# rfid-access-control.net
KiCad netlist of a schematic drawn in EAGLE
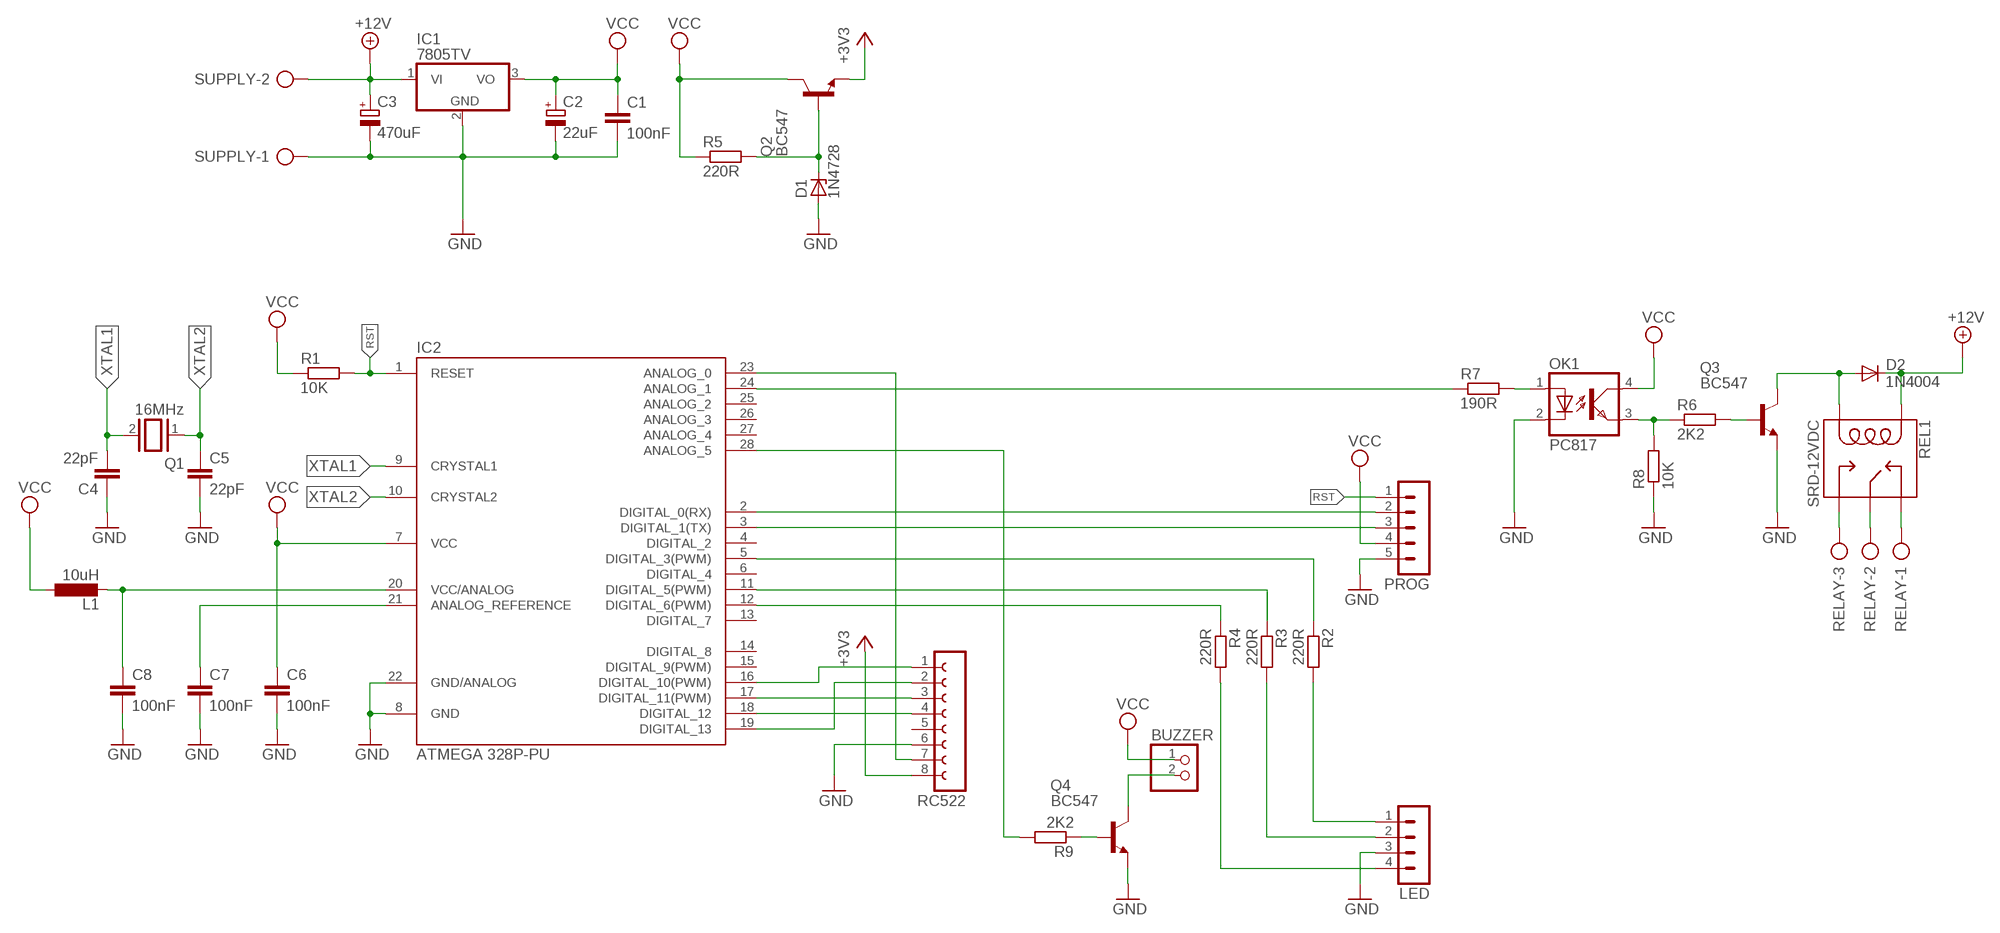
[diagram p0: schematic, sheet 1]

(export (version "E")
  (design (tool "Eeschema 10.0.6"))
  (components
    (comp (ref "BUZZER")
      (value "PINHD-1X2")
      (footprint "eagle-import:1X02")
      (libsource (lib "eagle-import") (part "PINHD-1X2"))
    )
    (comp (ref "C1")
      (value "100nF")
      (footprint "eagle-import:C025-025X050")
      (libsource (lib "eagle-import") (part "C-EU025-025X050"))
    )
    (comp (ref "C2")
      (value "22uF")
      (footprint "eagle-import:E2,5-7")
      (libsource (lib "eagle-import") (part "CPOL-EUE2.5-7"))
    )
    (comp (ref "C3")
      (value "470uF")
      (footprint "eagle-import:E2,5-7")
      (libsource (lib "eagle-import") (part "CPOL-EUE2.5-7"))
    )
    (comp (ref "C4")
      (value "22pF")
      (footprint "eagle-import:C025-025X050")
      (libsource (lib "eagle-import") (part "C-EU025-025X050"))
    )
    (comp (ref "C5")
      (value "22pF")
      (footprint "eagle-import:C025-025X050")
      (libsource (lib "eagle-import") (part "C-EU025-025X050"))
    )
    (comp (ref "C6")
      (value "100nF")
      (footprint "eagle-import:C025-025X050")
      (libsource (lib "eagle-import") (part "C-EU025-025X050"))
    )
    (comp (ref "C7")
      (value "100nF")
      (footprint "eagle-import:C025-025X050")
      (libsource (lib "eagle-import") (part "C-EU025-025X050"))
    )
    (comp (ref "C8")
      (value "100nF")
      (footprint "eagle-import:C025-025X050")
      (libsource (lib "eagle-import") (part "C-EU025-025X050"))
    )
    (comp (ref "D1")
      (value "1N4728")
      (footprint "eagle-import:DO41Z10")
      (libsource (lib "eagle-import") (part "1N4728"))
    )
    (comp (ref "D2")
      (value "1N4004")
      (footprint "eagle-import:DO41-10")
      (libsource (lib "eagle-import") (part "1N4004"))
    )
    (comp (ref "IC1")
      (value "7805TV")
      (footprint "eagle-import:TO220V")
      (libsource (lib "eagle-import") (part "78TV05"))
    )
    (comp (ref "IC2")
      (value "ATMEGA 328P-PU")
      (footprint "eagle-import:DIL28-3")
      (libsource (lib "eagle-import") (part "ATMEGA168-PU"))
    )
    (comp (ref "L1")
      (value "10uH")
      (footprint "eagle-import:0207_7")
      (libsource (lib "eagle-import") (part "L-EU0207/7"))
    )
    (comp (ref "LED")
      (value "MA04-1")
      (footprint "eagle-import:MA04-1")
      (libsource (lib "eagle-import") (part "MA04-1"))
    )
    (comp (ref "OK1")
      (value "PC817")
      (footprint "eagle-import:DIL04")
      (fields (field (name "MPN") "PC817X4J000F"))
      (libsource (lib "eagle-import") (part "PC817"))
    )
    (comp (ref "PROG")
      (value "MA05-1")
      (footprint "eagle-import:MA05-1")
      (libsource (lib "eagle-import") (part "MA05-1"))
    )
    (comp (ref "Q1")
      (value "16MHz")
      (footprint "eagle-import:QS")
      (libsource (lib "eagle-import") (part "XTAL/S"))
    )
    (comp (ref "Q2")
      (value "BC547")
      (footprint "eagle-import:TO92")
      (libsource (lib "eagle-import") (part "BC547"))
    )
    (comp (ref "Q3")
      (value "BC547")
      (footprint "eagle-import:TO92")
      (libsource (lib "eagle-import") (part "BC547"))
    )
    (comp (ref "Q4")
      (value "BC547")
      (footprint "eagle-import:TO92")
      (libsource (lib "eagle-import") (part "BC547"))
    )
    (comp (ref "R1")
      (value "10K")
      (footprint "eagle-import:0207_7")
      (libsource (lib "eagle-import") (part "R-EU_0207/7"))
    )
    (comp (ref "R2")
      (value "220R")
      (footprint "eagle-import:0207_7")
      (libsource (lib "eagle-import") (part "R-EU_0207/7"))
    )
    (comp (ref "R3")
      (value "220R")
      (footprint "eagle-import:0207_7")
      (libsource (lib "eagle-import") (part "R-EU_0207/7"))
    )
    (comp (ref "R4")
      (value "220R")
      (footprint "eagle-import:0207_7")
      (libsource (lib "eagle-import") (part "R-EU_0207/7"))
    )
    (comp (ref "R5")
      (value "220R")
      (footprint "eagle-import:0207_7")
      (libsource (lib "eagle-import") (part "R-EU_0207/7"))
    )
    (comp (ref "R6")
      (value "2K2")
      (footprint "eagle-import:0207_7")
      (libsource (lib "eagle-import") (part "R-EU_0207/7"))
    )
    (comp (ref "R7")
      (value "190R")
      (footprint "eagle-import:0207_7")
      (libsource (lib "eagle-import") (part "R-EU_0207/7"))
    )
    (comp (ref "R8")
      (value "10K")
      (footprint "eagle-import:0207_7")
      (libsource (lib "eagle-import") (part "R-EU_0207/7"))
    )
    (comp (ref "R9")
      (value "2K2")
      (footprint "eagle-import:0207_7")
      (libsource (lib "eagle-import") (part "R-EU_0207/7"))
    )
    (comp (ref "RC522")
      (value "FE08-1")
      (footprint "eagle-import:FE08")
      (libsource (lib "eagle-import") (part "FE08-1"))
    )
    (comp (ref "REL1")
      (value "SRD-12VDC")
      (footprint "eagle-import:SRD-05VDC-SL-C")
      (libsource (lib "eagle-import") (part "RELAYPTH"))
    )
    (comp (ref "RELAY")
      (value "AK500/3")
      (footprint "eagle-import:AK500_3")
      (libsource (lib "eagle-import") (part "AK500/3"))
    )
    (comp (ref "SUPPLY")
      (value "AK500/2")
      (footprint "eagle-import:AK500_2")
      (libsource (lib "eagle-import") (part "AK500/2"))
    )
  )
  (nets
    (net (code "1") (name "+3V3") (class "Default")
      (node (ref "Q2") (pin "1") (pinfunction "E_1") (pintype "passive"))
      (node (ref "RC522") (pin "8") (pinfunction "8_8") (pintype "passive"))
    )
    (net (code "2") (name "+12V") (class "Default")
      (node (ref "C3") (pin "+") (pinfunction "+_+") (pintype "passive"))
      (node (ref "D2") (pin "C") (pinfunction "C_C") (pintype "passive"))
      (node (ref "IC1") (pin "1") (pinfunction "VI_1") (pintype "input"))
      (node (ref "REL1") (pin "COIL1") (pinfunction "COIL1_COIL1") (pintype "bidirectional"))
      (node (ref "SUPPLY") (pin "2") (pinfunction "KL_2") (pintype "passive"))
    )
    (net (code "3") (name "GND") (class "Default")
      (node (ref "C1") (pin "2") (pinfunction "2_2") (pintype "passive"))
      (node (ref "C2") (pin "-") (pinfunction "-_-") (pintype "passive"))
      (node (ref "C3") (pin "-") (pinfunction "-_-") (pintype "passive"))
      (node (ref "C4") (pin "1") (pinfunction "1_1") (pintype "passive"))
      (node (ref "C5") (pin "2") (pinfunction "2_2") (pintype "passive"))
      (node (ref "C6") (pin "2") (pinfunction "2_2") (pintype "passive"))
      (node (ref "C7") (pin "2") (pinfunction "2_2") (pintype "passive"))
      (node (ref "C8") (pin "2") (pinfunction "2_2") (pintype "passive"))
      (node (ref "D1") (pin "A") (pinfunction "A_A") (pintype "passive"))
      (node (ref "IC1") (pin "2") (pinfunction "GND_2") (pintype "passive"))
      (node (ref "IC2") (pin "22") (pinfunction "GND/ANALOG_22") (pintype "power_in"))
      (node (ref "IC2") (pin "8") (pinfunction "GND_8") (pintype "power_in"))
      (node (ref "LED") (pin "3") (pinfunction "3_3") (pintype "passive"))
      (node (ref "OK1") (pin "2") (pinfunction "C_2") (pintype "passive"))
      (node (ref "PROG") (pin "5") (pinfunction "5_5") (pintype "passive"))
      (node (ref "Q3") (pin "1") (pinfunction "E_1") (pintype "passive"))
      (node (ref "Q4") (pin "1") (pinfunction "E_1") (pintype "passive"))
      (node (ref "R8") (pin "1") (pinfunction "1_1") (pintype "passive"))
      (node (ref "RC522") (pin "6") (pinfunction "6_6") (pintype "passive"))
      (node (ref "SUPPLY") (pin "1") (pinfunction "KL_1") (pintype "passive"))
    )
    (net (code "4") (name "Net-(IC2-ANALOG_0)") (class "Default")
      (node (ref "IC2") (pin "23") (pinfunction "ANALOG_0_23") (pintype "bidirectional"))
      (node (ref "RC522") (pin "7") (pinfunction "7_7") (pintype "passive"))
    )
    (net (code "5") (name "Net-(IC2-ANALOG_1)") (class "Default")
      (node (ref "IC2") (pin "24") (pinfunction "ANALOG_1_24") (pintype "bidirectional"))
      (node (ref "R7") (pin "1") (pinfunction "1_1") (pintype "passive"))
    )
    (net (code "6") (name "Net-(IC2-ANALOG_5)") (class "Default")
      (node (ref "IC2") (pin "28") (pinfunction "ANALOG_5_28") (pintype "bidirectional"))
      (node (ref "R9") (pin "2") (pinfunction "2_2") (pintype "passive"))
    )
    (net (code "7") (name "Net-(IC2-ANALOG_REFERENCE)") (class "Default")
      (node (ref "C7") (pin "1") (pinfunction "1_1") (pintype "passive"))
      (node (ref "IC2") (pin "21") (pinfunction "ANALOG_REFERENCE_21") (pintype "passive"))
    )
    (net (code "8") (name "Net-(IC2-DIGITAL_0(RX))") (class "Default")
      (node (ref "IC2") (pin "2") (pinfunction "DIGITAL_0(RX)_2") (pintype "bidirectional"))
      (node (ref "PROG") (pin "2") (pinfunction "2_2") (pintype "passive"))
    )
    (net (code "9") (name "Net-(IC2-DIGITAL_1(TX))") (class "Default")
      (node (ref "IC2") (pin "3") (pinfunction "DIGITAL_1(TX)_3") (pintype "bidirectional"))
      (node (ref "PROG") (pin "3") (pinfunction "3_3") (pintype "passive"))
    )
    (net (code "10") (name "Net-(IC2-DIGITAL_3(PWM))") (class "Default")
      (node (ref "IC2") (pin "5") (pinfunction "DIGITAL_3(PWM)_5") (pintype "bidirectional"))
      (node (ref "R2") (pin "1") (pinfunction "1_1") (pintype "passive"))
    )
    (net (code "11") (name "Net-(IC2-DIGITAL_5(PWM))") (class "Default")
      (node (ref "IC2") (pin "11") (pinfunction "DIGITAL_5(PWM)_11") (pintype "bidirectional"))
      (node (ref "R3") (pin "1") (pinfunction "1_1") (pintype "passive"))
    )
    (net (code "12") (name "Net-(IC2-DIGITAL_6(PWM))") (class "Default")
      (node (ref "IC2") (pin "12") (pinfunction "DIGITAL_6(PWM)_12") (pintype "bidirectional"))
      (node (ref "R4") (pin "1") (pinfunction "1_1") (pintype "passive"))
    )
    (net (code "13") (name "Net-(IC2-DIGITAL_10(PWM))") (class "Default")
      (node (ref "IC2") (pin "16") (pinfunction "DIGITAL_10(PWM)_16") (pintype "bidirectional"))
      (node (ref "RC522") (pin "1") (pinfunction "1_1") (pintype "passive"))
    )
    (net (code "14") (name "Net-(IC2-DIGITAL_11(PWM))") (class "Default")
      (node (ref "IC2") (pin "17") (pinfunction "DIGITAL_11(PWM)_17") (pintype "bidirectional"))
      (node (ref "RC522") (pin "3") (pinfunction "3_3") (pintype "passive"))
    )
    (net (code "15") (name "Net-(IC2-DIGITAL_12)") (class "Default")
      (node (ref "IC2") (pin "18") (pinfunction "DIGITAL_12_18") (pintype "bidirectional"))
      (node (ref "RC522") (pin "4") (pinfunction "4_4") (pintype "passive"))
    )
    (net (code "16") (name "Net-(IC2-DIGITAL_13)") (class "Default")
      (node (ref "IC2") (pin "19") (pinfunction "DIGITAL_13_19") (pintype "bidirectional"))
      (node (ref "RC522") (pin "2") (pinfunction "2_2") (pintype "passive"))
    )
    (net (code "17") (name "Net-(IC2-VCC{slash}ANALOG)") (class "Default")
      (node (ref "C8") (pin "1") (pinfunction "1_1") (pintype "passive"))
      (node (ref "IC2") (pin "20") (pinfunction "VCC/ANALOG_20") (pintype "passive"))
      (node (ref "L1") (pin "2") (pinfunction "2_2") (pintype "passive"))
    )
    (net (code "18") (name "Net-(LED-Pad1)") (class "Default")
      (node (ref "LED") (pin "1") (pinfunction "1_1") (pintype "passive"))
      (node (ref "R2") (pin "2") (pinfunction "2_2") (pintype "passive"))
    )
    (net (code "19") (name "Net-(LED-Pad2)") (class "Default")
      (node (ref "LED") (pin "2") (pinfunction "2_2") (pintype "passive"))
      (node (ref "R3") (pin "2") (pinfunction "2_2") (pintype "passive"))
    )
    (net (code "20") (name "Net-(LED-Pad4)") (class "Default")
      (node (ref "LED") (pin "4") (pinfunction "4_4") (pintype "passive"))
      (node (ref "R4") (pin "2") (pinfunction "2_2") (pintype "passive"))
    )
    (net (code "21") (name "Net-(OK1-A)") (class "Default")
      (node (ref "OK1") (pin "1") (pinfunction "A_1") (pintype "passive"))
      (node (ref "R7") (pin "2") (pinfunction "2_2") (pintype "passive"))
    )
    (net (code "22") (name "Net-(OK1-EMIT)") (class "Default")
      (node (ref "OK1") (pin "3") (pinfunction "EMIT_3") (pintype "passive"))
      (node (ref "R6") (pin "1") (pinfunction "1_1") (pintype "passive"))
      (node (ref "R8") (pin "2") (pinfunction "2_2") (pintype "passive"))
    )
    (net (code "23") (name "Net-(Q2-B)") (class "Default")
      (node (ref "D1") (pin "C") (pinfunction "C_C") (pintype "passive"))
      (node (ref "Q2") (pin "2") (pinfunction "B_2") (pintype "passive"))
      (node (ref "R5") (pin "2") (pinfunction "2_2") (pintype "passive"))
    )
    (net (code "24") (name "Net-(Q3-B)") (class "Default")
      (node (ref "Q3") (pin "2") (pinfunction "B_2") (pintype "passive"))
      (node (ref "R6") (pin "2") (pinfunction "2_2") (pintype "passive"))
    )
    (net (code "25") (name "Net-(Q3-C)") (class "Default")
      (node (ref "D2") (pin "A") (pinfunction "A_A") (pintype "passive"))
      (node (ref "Q3") (pin "3") (pinfunction "C_3") (pintype "passive"))
      (node (ref "REL1") (pin "COIL0") (pinfunction "COIL0_COIL0") (pintype "bidirectional"))
    )
    (net (code "26") (name "Net-(Q4-B)") (class "Default")
      (node (ref "Q4") (pin "2") (pinfunction "B_2") (pintype "passive"))
      (node (ref "R9") (pin "1") (pinfunction "1_1") (pintype "passive"))
    )
    (net (code "27") (name "Net-(Q4-C)") (class "Default")
      (node (ref "BUZZER") (pin "2") (pinfunction "2_2") (pintype "passive"))
      (node (ref "Q4") (pin "3") (pinfunction "C_3") (pintype "passive"))
    )
    (net (code "28") (name "Net-(REL1-SWCLOSE)") (class "Default")
      (node (ref "REL1") (pin "SWCLOSED") (pinfunction "SWCLOSE_SWCLOSED") (pintype "bidirectional"))
      (node (ref "RELAY") (pin "1") (pinfunction "KL_1") (pintype "passive"))
    )
    (net (code "29") (name "Net-(RELAYB-KL)") (class "Default")
      (node (ref "REL1") (pin "SWCOMMON") (pinfunction "SWCOMMON_SWCOMMON") (pintype "bidirectional"))
      (node (ref "RELAY") (pin "2") (pinfunction "KL_2") (pintype "passive"))
    )
    (net (code "30") (name "Net-(RELAYC-KL)") (class "Default")
      (node (ref "REL1") (pin "SWOPEN") (pinfunction "SWOPEN_SWOPEN") (pintype "bidirectional"))
      (node (ref "RELAY") (pin "3") (pinfunction "KL_3") (pintype "passive"))
    )
    (net (code "31") (name "RST") (class "Default")
      (node (ref "IC2") (pin "1") (pinfunction "RESET_1") (pintype "bidirectional"))
      (node (ref "PROG") (pin "1") (pinfunction "1_1") (pintype "passive"))
      (node (ref "R1") (pin "2") (pinfunction "2_2") (pintype "passive"))
    )
    (net (code "32") (name "VCC") (class "Default")
      (node (ref "BUZZER") (pin "1") (pinfunction "1_1") (pintype "passive"))
      (node (ref "C1") (pin "1") (pinfunction "1_1") (pintype "passive"))
      (node (ref "C2") (pin "+") (pinfunction "+_+") (pintype "passive"))
      (node (ref "C6") (pin "1") (pinfunction "1_1") (pintype "passive"))
      (node (ref "IC1") (pin "3") (pinfunction "VO_3") (pintype "passive"))
      (node (ref "IC2") (pin "7") (pinfunction "VCC_7") (pintype "power_in"))
      (node (ref "L1") (pin "1") (pinfunction "1_1") (pintype "passive"))
      (node (ref "OK1") (pin "4") (pinfunction "COL_4") (pintype "passive"))
      (node (ref "PROG") (pin "4") (pinfunction "4_4") (pintype "passive"))
      (node (ref "Q2") (pin "3") (pinfunction "C_3") (pintype "passive"))
      (node (ref "R1") (pin "1") (pinfunction "1_1") (pintype "passive"))
      (node (ref "R5") (pin "1") (pinfunction "1_1") (pintype "passive"))
    )
    (net (code "33") (name "XTAL1") (class "Default")
      (node (ref "C4") (pin "2") (pinfunction "2_2") (pintype "passive"))
      (node (ref "IC2") (pin "9") (pinfunction "CRYSTAL1_9") (pintype "bidirectional"))
      (node (ref "Q1") (pin "2") (pinfunction "2_2") (pintype "passive"))
    )
    (net (code "34") (name "XTAL2") (class "Default")
      (node (ref "C5") (pin "1") (pinfunction "1_1") (pintype "passive"))
      (node (ref "IC2") (pin "10") (pinfunction "CRYSTAL2_10") (pintype "bidirectional"))
      (node (ref "Q1") (pin "1") (pinfunction "1_1") (pintype "passive"))
    )
    (net (code "35") (name "unconnected-(IC2-ANALOG_2-Pad25)") (class "Default")
      (node (ref "IC2") (pin "25") (pinfunction "ANALOG_2_25") (pintype "bidirectional"))
    )
    (net (code "36") (name "unconnected-(IC2-ANALOG_3-Pad26)") (class "Default")
      (node (ref "IC2") (pin "26") (pinfunction "ANALOG_3_26") (pintype "bidirectional"))
    )
    (net (code "37") (name "unconnected-(IC2-ANALOG_4-Pad27)") (class "Default")
      (node (ref "IC2") (pin "27") (pinfunction "ANALOG_4_27") (pintype "bidirectional"))
    )
    (net (code "38") (name "unconnected-(IC2-DIGITAL_2-Pad4)") (class "Default")
      (node (ref "IC2") (pin "4") (pinfunction "DIGITAL_2_4") (pintype "bidirectional"))
    )
    (net (code "39") (name "unconnected-(IC2-DIGITAL_4-Pad6)") (class "Default")
      (node (ref "IC2") (pin "6") (pinfunction "DIGITAL_4_6") (pintype "bidirectional"))
    )
    (net (code "40") (name "unconnected-(IC2-DIGITAL_7-Pad13)") (class "Default")
      (node (ref "IC2") (pin "13") (pinfunction "DIGITAL_7_13") (pintype "bidirectional"))
    )
    (net (code "41") (name "unconnected-(IC2-DIGITAL_8-Pad14)") (class "Default")
      (node (ref "IC2") (pin "14") (pinfunction "DIGITAL_8_14") (pintype "bidirectional"))
    )
    (net (code "42") (name "unconnected-(IC2-DIGITAL_9(PWM)-Pad15)") (class "Default")
      (node (ref "IC2") (pin "15") (pinfunction "DIGITAL_9(PWM)_15") (pintype "bidirectional"))
    )
    (net (code "43") (name "unconnected-(RC522-Pad5)") (class "Default")
      (node (ref "RC522") (pin "5") (pinfunction "5_5") (pintype "passive"))
    )
  )
)
